# Esquematico.net
KiCad netlist of a schematic drawn in Altium Designer
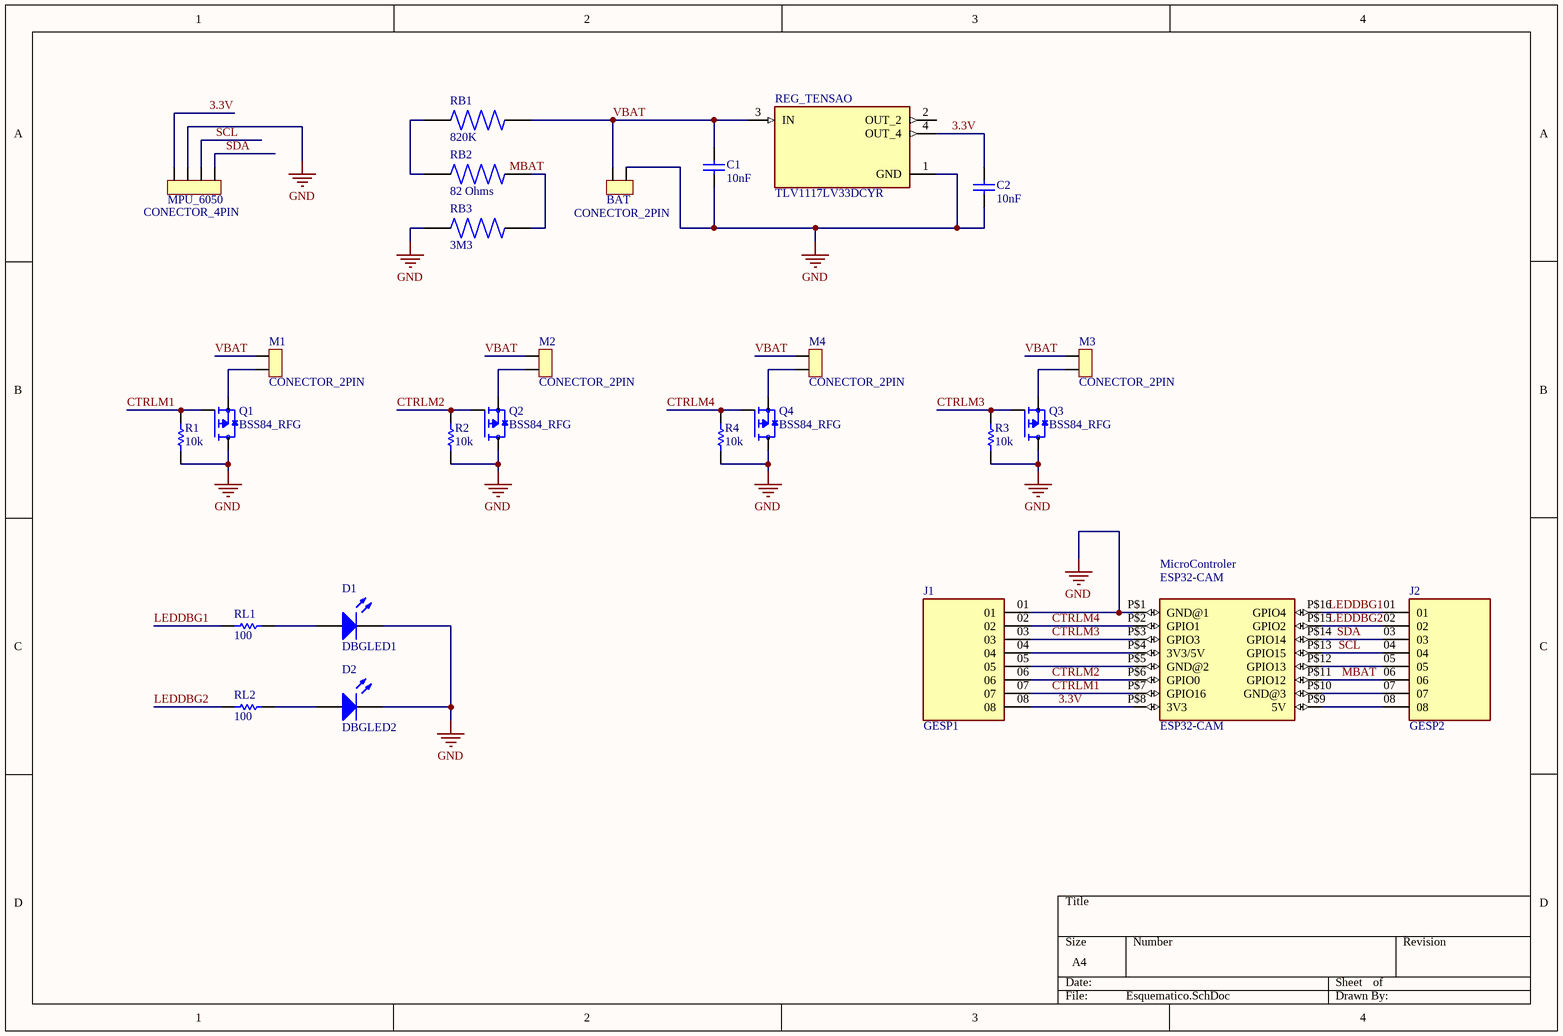
[diagram p0: Esquematico.SchDoc]

(export (version "E")
  (design (tool "Eeschema 10.0.6"))
  (components
    (comp (ref "BAT")
      (value "CONECTOR_2PIN")
      (footprint "CON2")
      (libsource (lib "") (part "CONECTOR_2PIN_1"))
    )
    (comp (ref "C1")
      (value "CAP")
      (footprint "CAP 0805")
      (description "Capacitor")
      (fields (field (name "VALOR") "10nF"))
      (libsource (lib "Biblioteca Trincabotz") (part "CAP. CERÂMICO"))
    )
    (comp (ref "C2")
      (value "CAP")
      (footprint "CAP 0805")
      (description "Capacitor")
      (fields (field (name "VALOR") "10nF"))
      (libsource (lib "Biblioteca Trincabotz") (part "CAP. CERÂMICO"))
    )
    (comp (ref "D1")
      (value "DBGLED1")
      (footprint "LED 0805")
      (libsource (lib "Biblioteca Trincabotz (1)") (part "LED"))
    )
    (comp (ref "D2")
      (value "DBGLED2")
      (footprint "LED 0805")
      (libsource (lib "Biblioteca Trincabotz (1)") (part "LED"))
    )
    (comp (ref "J1")
      (value "GESP1")
      (footprint "SAMTEC_SS-108-T-2")
      (description "SS Series .100 Single Row Screw Machine Socket Strip")
      (fields (field (name "MP") "SS-108-T-2") (field (name "MF") "Samtec"))
      (libsource (lib "") (part "SS-108-T-2_1"))
    )
    (comp (ref "J2")
      (value "GESP2")
      (footprint "SAMTEC_SS-108-T-2")
      (description "SS Series .100 Single Row Screw Machine Socket Strip")
      (fields (field (name "MP") "SS-108-T-2") (field (name "MF") "Samtec"))
      (libsource (lib "8PIN-CONECTOR") (part "SS-108-T-2"))
    )
    (comp (ref "M1")
      (value "CONECTOR_2PIN")
      (footprint "CON2")
      (libsource (lib "Biblioteca Trincabotz") (part "CONECTOR_2PIN"))
    )
    (comp (ref "M2")
      (value "CONECTOR_2PIN")
      (footprint "CON2")
      (libsource (lib "Biblioteca Trincabotz") (part "CONECTOR_2PIN"))
    )
    (comp (ref "M3")
      (value "CONECTOR_2PIN")
      (footprint "CON2")
      (libsource (lib "Biblioteca Trincabotz") (part "CONECTOR_2PIN"))
    )
    (comp (ref "M4")
      (value "CONECTOR_2PIN")
      (footprint "CON2")
      (libsource (lib "Biblioteca Trincabotz") (part "CONECTOR_2PIN"))
    )
    (comp (ref "MicroControler")
      (value "ESP32-CAM")
      (footprint "ESP32-CAM")
      (fields (field (name "MF") "AI-Thinker"))
      (libsource (lib "ESP32_CAM") (part "ESP32-CAM"))
    )
    (comp (ref "MPU_6050")
      (value "CONECTOR_4PIN")
      (footprint "CON4")
      (libsource (lib "Biblioteca Trincabotz") (part "CONECTOR_4PIN"))
    )
    (comp (ref "Q1")
      (value "BSS84_RFG")
      (footprint "SOT95P240X115-3N")
      (description "-60V, -0.15A, Single P-Channel Small-signal MOSFETs")
      (fields (field (name "MF") "Taiwan Semiconductor") (field (name "MP") "BSS84 RFG"))
      (libsource (lib "MOSFET_SMD") (part "BSS84_RFG"))
    )
    (comp (ref "Q2")
      (value "BSS84_RFG")
      (footprint "SOT95P240X115-3N")
      (description "-60V, -0.15A, Single P-Channel Small-signal MOSFETs")
      (fields (field (name "MF") "Taiwan Semiconductor") (field (name "MP") "BSS84 RFG"))
      (libsource (lib "MOSFET_SMD") (part "BSS84_RFG"))
    )
    (comp (ref "Q3")
      (value "BSS84_RFG")
      (footprint "SOT95P240X115-3N")
      (description "-60V, -0.15A, Single P-Channel Small-signal MOSFETs")
      (fields (field (name "MF") "Taiwan Semiconductor") (field (name "MP") "BSS84 RFG"))
      (libsource (lib "MOSFET_SMD") (part "BSS84_RFG"))
    )
    (comp (ref "Q4")
      (value "BSS84_RFG")
      (footprint "SOT95P240X115-3N")
      (description "-60V, -0.15A, Single P-Channel Small-signal MOSFETs")
      (fields (field (name "MF") "Taiwan Semiconductor") (field (name "MP") "BSS84 RFG"))
      (libsource (lib "MOSFET_SMD") (part "BSS84_RFG"))
    )
    (comp (ref "R1")
      (value "10k")
      (footprint "RES 0805")
      (description "Resistor")
      (fields (field (name "Comment") "RESISTOR"))
      (libsource (lib "Biblioteca Trincabotz") (part "RESISTOR"))
    )
    (comp (ref "R2")
      (value "10k")
      (footprint "RES 0805")
      (description "Resistor")
      (fields (field (name "Comment") "RESISTOR"))
      (libsource (lib "Biblioteca Trincabotz") (part "RESISTOR"))
    )
    (comp (ref "R3")
      (value "10k")
      (footprint "RES 0805")
      (description "Resistor")
      (fields (field (name "Comment") "RESISTOR"))
      (libsource (lib "Biblioteca Trincabotz") (part "RESISTOR"))
    )
    (comp (ref "R4")
      (value "10k")
      (footprint "RES 0805")
      (description "Resistor")
      (fields (field (name "Comment") "RESISTOR"))
      (libsource (lib "Biblioteca Trincabotz") (part "RESISTOR"))
    )
    (comp (ref "RB1")
      (value "820K")
      (footprint "RESAD700W45L350D185")
      (description "1 MOhms Â±5% 0.25W, 1/4W Through Hole Resistor Axial - Carbon Film")
      (fields (field (name "MF") "TE Connectivity") (field (name "MP") "3-1623927-1"))
      (libsource (lib "ResistorTHL") (part "3-1623927-1"))
    )
    (comp (ref "RB2")
      (value "82 Ohms")
      (footprint "RESAD700W45L350D185")
      (description "1 MOhms Â±5% 0.25W, 1/4W Through Hole Resistor Axial - Carbon Film")
      (fields (field (name "MF") "TE Connectivity") (field (name "MP") "3-1623927-1"))
      (libsource (lib "ResistorTHL") (part "3-1623927-1"))
    )
    (comp (ref "RB3")
      (value "3M3")
      (footprint "RESAD700W45L350D185")
      (description "1 MOhms Â±5% 0.25W, 1/4W Through Hole Resistor Axial - Carbon Film")
      (fields (field (name "MF") "TE Connectivity") (field (name "MP") "3-1623927-1"))
      (libsource (lib "ResistorTHL") (part "3-1623927-1"))
    )
    (comp (ref "REG_TENSAO")
      (value "TLV1117LV33DCYR")
      (footprint "VREG_TLV1117LV33DCYR")
      (description "1-A, low-dropout voltage regulator")
      (fields (field (name "MF") "Texas Instruments"))
      (libsource (lib "REG_TENSAO") (part "TLV1117LV33DCYR"))
    )
    (comp (ref "RL1")
      (value "100")
      (footprint "RES 0805")
      (description "Resistor")
      (fields (field (name "Comment") "RESISTOR"))
      (libsource (lib "Biblioteca Trincabotz (1)") (part "RESISTOR"))
    )
    (comp (ref "RL2")
      (value "100")
      (footprint "RES 0805")
      (description "Resistor")
      (fields (field (name "Comment") "RESISTOR"))
      (libsource (lib "Biblioteca Trincabotz (1)") (part "RESISTOR"))
    )
  )
  (nets
    (net (code "1") (name "/3.3V") (class "Default")
      (node (ref "C2") (pin "2") (pinfunction "2_2") (pintype "passive"))
      (node (ref "J1") (pin "08") (pinfunction "08_08") (pintype "passive"))
      (node (ref "MPU_6050") (pin "1") (pinfunction "1_1") (pintype "passive"))
      (node (ref "MicroControler") (pin "P$8") (pinfunction "3V3_P$8") (pintype "bidirectional"))
      (node (ref "REG_TENSAO") (pin "4") (pinfunction "OUT_4_4") (pintype "output"))
    )
    (net (code "2") (name "/CTRLM1") (class "Default")
      (node (ref "J1") (pin "07") (pinfunction "07_07") (pintype "passive"))
      (node (ref "MicroControler") (pin "P$7") (pinfunction "GPIO16_P$7") (pintype "bidirectional"))
      (node (ref "Q1") (pin "1") (pinfunction "G_1") (pintype "passive"))
      (node (ref "R1") (pin "2") (pinfunction "2_2") (pintype "passive"))
    )
    (net (code "3") (name "/CTRLM2") (class "Default")
      (node (ref "J1") (pin "06") (pinfunction "06_06") (pintype "passive"))
      (node (ref "MicroControler") (pin "P$6") (pinfunction "GPIO0_P$6") (pintype "bidirectional"))
      (node (ref "Q2") (pin "1") (pinfunction "G_1") (pintype "passive"))
      (node (ref "R2") (pin "2") (pinfunction "2_2") (pintype "passive"))
    )
    (net (code "4") (name "/CTRLM3") (class "Default")
      (node (ref "J1") (pin "03") (pinfunction "03_03") (pintype "passive"))
      (node (ref "MicroControler") (pin "P$3") (pinfunction "GPIO3_P$3") (pintype "bidirectional"))
      (node (ref "Q3") (pin "1") (pinfunction "G_1") (pintype "passive"))
      (node (ref "R3") (pin "2") (pinfunction "2_2") (pintype "passive"))
    )
    (net (code "5") (name "/CTRLM4") (class "Default")
      (node (ref "J1") (pin "02") (pinfunction "02_02") (pintype "passive"))
      (node (ref "MicroControler") (pin "P$2") (pinfunction "GPIO1_P$2") (pintype "bidirectional"))
      (node (ref "Q4") (pin "1") (pinfunction "G_1") (pintype "passive"))
      (node (ref "R4") (pin "2") (pinfunction "2_2") (pintype "passive"))
    )
    (net (code "6") (name "/LEDDBG1") (class "Default")
      (node (ref "J2") (pin "01") (pinfunction "01_01") (pintype "passive"))
      (node (ref "MicroControler") (pin "P$16") (pinfunction "GPIO4_P$16") (pintype "bidirectional"))
      (node (ref "RL1") (pin "1") (pinfunction "1_1") (pintype "passive"))
    )
    (net (code "7") (name "/LEDDBG2") (class "Default")
      (node (ref "J2") (pin "02") (pinfunction "02_02") (pintype "passive"))
      (node (ref "MicroControler") (pin "P$15") (pinfunction "GPIO2_P$15") (pintype "bidirectional"))
      (node (ref "RL2") (pin "1") (pinfunction "1_1") (pintype "passive"))
    )
    (net (code "8") (name "/MBAT") (class "Default")
      (node (ref "J2") (pin "06") (pinfunction "06_06") (pintype "passive"))
      (node (ref "MicroControler") (pin "P$11") (pinfunction "GPIO12_P$11") (pintype "bidirectional"))
      (node (ref "RB2") (pin "2") (pinfunction "2_2") (pintype "passive"))
      (node (ref "RB3") (pin "2") (pinfunction "2_2") (pintype "passive"))
    )
    (net (code "9") (name "/SCL") (class "Default")
      (node (ref "J2") (pin "04") (pinfunction "04_04") (pintype "passive"))
      (node (ref "MPU_6050") (pin "3") (pinfunction "3_3") (pintype "passive"))
      (node (ref "MicroControler") (pin "P$13") (pinfunction "GPIO15_P$13") (pintype "bidirectional"))
    )
    (net (code "10") (name "/SDA") (class "Default")
      (node (ref "J2") (pin "03") (pinfunction "03_03") (pintype "passive"))
      (node (ref "MPU_6050") (pin "4") (pinfunction "4_4") (pintype "passive"))
      (node (ref "MicroControler") (pin "P$14") (pinfunction "GPIO14_P$14") (pintype "bidirectional"))
    )
    (net (code "11") (name "/VBAT") (class "Default")
      (node (ref "BAT") (pin "1") (pinfunction "1_1") (pintype "passive"))
      (node (ref "C1") (pin "2") (pinfunction "2_2") (pintype "passive"))
      (node (ref "M1") (pin "2") (pinfunction "2_2") (pintype "passive"))
      (node (ref "M2") (pin "2") (pinfunction "2_2") (pintype "passive"))
      (node (ref "M3") (pin "2") (pinfunction "2_2") (pintype "passive"))
      (node (ref "M4") (pin "2") (pinfunction "2_2") (pintype "passive"))
      (node (ref "RB1") (pin "2") (pinfunction "2_2") (pintype "passive"))
      (node (ref "REG_TENSAO") (pin "3") (pinfunction "IN_3") (pintype "input"))
    )
    (net (code "12") (name "GND") (class "Default")
      (node (ref "BAT") (pin "2") (pinfunction "2_2") (pintype "passive"))
      (node (ref "C1") (pin "1") (pinfunction "1_1") (pintype "passive"))
      (node (ref "C2") (pin "1") (pinfunction "1_1") (pintype "passive"))
      (node (ref "D1") (pin "2") (pinfunction "K_2") (pintype "passive"))
      (node (ref "D2") (pin "2") (pinfunction "K_2") (pintype "passive"))
      (node (ref "J1") (pin "01") (pinfunction "01_01") (pintype "passive"))
      (node (ref "MPU_6050") (pin "2") (pinfunction "2_2") (pintype "passive"))
      (node (ref "MicroControler") (pin "P$1") (pinfunction "GND@1_P$1") (pintype "bidirectional"))
      (node (ref "Q1") (pin "3") (pinfunction "D_3") (pintype "passive"))
      (node (ref "Q2") (pin "3") (pinfunction "D_3") (pintype "passive"))
      (node (ref "Q3") (pin "3") (pinfunction "D_3") (pintype "passive"))
      (node (ref "Q4") (pin "3") (pinfunction "D_3") (pintype "passive"))
      (node (ref "R1") (pin "1") (pinfunction "1_1") (pintype "passive"))
      (node (ref "R2") (pin "1") (pinfunction "1_1") (pintype "passive"))
      (node (ref "R3") (pin "1") (pinfunction "1_1") (pintype "passive"))
      (node (ref "R4") (pin "1") (pinfunction "1_1") (pintype "passive"))
      (node (ref "RB3") (pin "1") (pinfunction "1_1") (pintype "passive"))
      (node (ref "REG_TENSAO") (pin "1") (pinfunction "GND_1") (pintype "power_in"))
    )
    (net (code "13") (name "Net-(D1-A)") (class "Default")
      (node (ref "D1") (pin "1") (pinfunction "A_1") (pintype "passive"))
      (node (ref "RL1") (pin "2") (pinfunction "2_2") (pintype "passive"))
    )
    (net (code "14") (name "Net-(D2-A)") (class "Default")
      (node (ref "D2") (pin "1") (pinfunction "A_1") (pintype "passive"))
      (node (ref "RL2") (pin "2") (pinfunction "2_2") (pintype "passive"))
    )
    (net (code "15") (name "Net-(MicroControler-3V3{slash}5V)") (class "Default")
      (node (ref "J1") (pin "04") (pinfunction "04_04") (pintype "passive"))
      (node (ref "MicroControler") (pin "P$4") (pinfunction "3V3/5V_P$4") (pintype "bidirectional"))
    )
    (net (code "16") (name "Net-(MicroControler-5V)") (class "Default")
      (node (ref "J2") (pin "08") (pinfunction "08_08") (pintype "passive"))
      (node (ref "MicroControler") (pin "P$9") (pinfunction "5V_P$9") (pintype "bidirectional"))
    )
    (net (code "17") (name "Net-(MicroControler-GND@2)") (class "Default")
      (node (ref "J1") (pin "05") (pinfunction "05_05") (pintype "passive"))
      (node (ref "MicroControler") (pin "P$5") (pinfunction "GND@2_P$5") (pintype "bidirectional"))
    )
    (net (code "18") (name "Net-(MicroControler-GND@3)") (class "Default")
      (node (ref "J2") (pin "07") (pinfunction "07_07") (pintype "passive"))
      (node (ref "MicroControler") (pin "P$10") (pinfunction "GND@3_P$10") (pintype "bidirectional"))
    )
    (net (code "19") (name "Net-(MicroControler-GPIO13)") (class "Default")
      (node (ref "J2") (pin "05") (pinfunction "05_05") (pintype "passive"))
      (node (ref "MicroControler") (pin "P$12") (pinfunction "GPIO13_P$12") (pintype "bidirectional"))
    )
    (net (code "20") (name "Net-(Q1-S)") (class "Default")
      (node (ref "M1") (pin "1") (pinfunction "1_1") (pintype "passive"))
      (node (ref "Q1") (pin "2") (pinfunction "S_2") (pintype "passive"))
    )
    (net (code "21") (name "Net-(Q2-S)") (class "Default")
      (node (ref "M2") (pin "1") (pinfunction "1_1") (pintype "passive"))
      (node (ref "Q2") (pin "2") (pinfunction "S_2") (pintype "passive"))
    )
    (net (code "22") (name "Net-(Q3-S)") (class "Default")
      (node (ref "M3") (pin "1") (pinfunction "1_1") (pintype "passive"))
      (node (ref "Q3") (pin "2") (pinfunction "S_2") (pintype "passive"))
    )
    (net (code "23") (name "Net-(Q4-S)") (class "Default")
      (node (ref "M4") (pin "1") (pinfunction "1_1") (pintype "passive"))
      (node (ref "Q4") (pin "2") (pinfunction "S_2") (pintype "passive"))
    )
    (net (code "24") (name "Net-(RB1-Pad1)") (class "Default")
      (node (ref "RB1") (pin "1") (pinfunction "1_1") (pintype "passive"))
      (node (ref "RB2") (pin "1") (pinfunction "1_1") (pintype "passive"))
    )
    (net (code "25") (name "unconnected-(REG_TENSAO-OUT_2-Pad2)") (class "Default")
      (node (ref "REG_TENSAO") (pin "2") (pinfunction "OUT_2_2") (pintype "output"))
    )
  )
)
